# Sheet1.net
KiCad netlist of a schematic drawn in Altium Designer
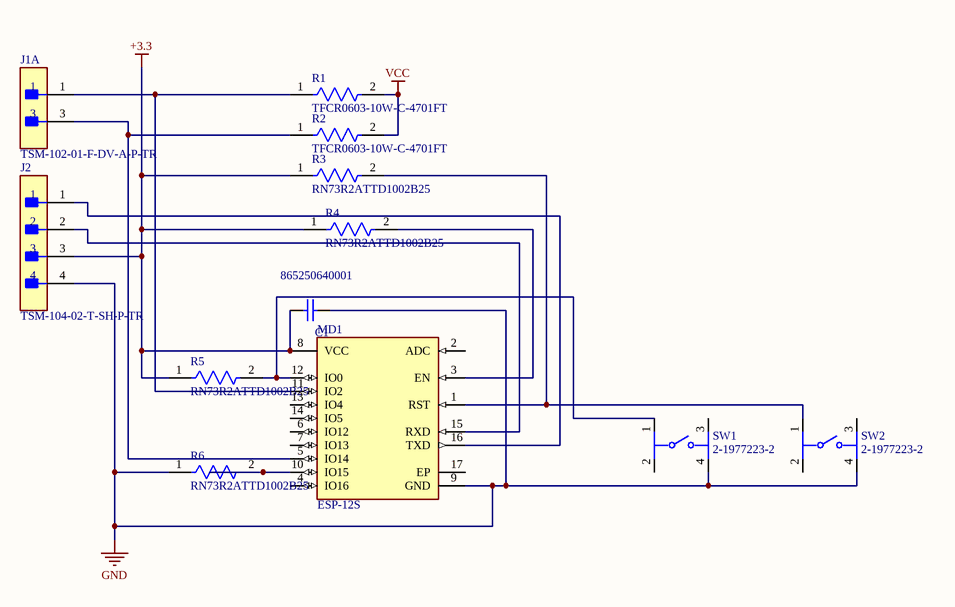
[diagram p0: Sheet1.SchDoc]

(export (version "E")
  (design (tool "Eeschema 10.0.6"))
  (components
    (comp (ref "C1")
      (value "865250640001")
      (footprint "WCAP-ASNP_D4H5.5")
      (description "WCAP-ASNP Aluminum Electrolytic Capacitors")
      (fields (field (name "TOLERANCE") "20%"))
      (libsource (lib "Altium Content Vault") (part "Capacitor_Non-Polarized"))
    )
    (comp (ref "J1")
      (value "TSM-102-01-F-DV-A-P-TR")
      (footprint "FP-TSM-102-01-F-DV-A-P-TR-MFG")
      (description "TSM-102-01-F-DV-A-P-TR .100\" Surface Mount Terminal Strip Rohs Compliant: Yes")
      (libsource (lib "Altium Content Vault") (part "1621473add15499e993d6bbd36d0f06"))
    )
    (comp (ref "J2")
      (value "TSM-104-02-T-SH-P-TR")
      (footprint "FP-TSM-104-02-T-SH-P-TR-MFG")
      (description "CONN HEADER SMD R/A 4POS 2.54MM")
      (libsource (lib "Altium Content Vault") (part "299a8cea1bdcbc3624fe62c390fa72c"))
    )
    (comp (ref "MD1")
      (value "ESP-12S")
      (footprint "FP-ESP-12S-MFG")
      (description "RX TXRX MOD WIFI PCB TRACE SMD")
      (libsource (lib "Altium Content Vault") (part "0473e498d6bc78f349d0f2898a8422c"))
    )
    (comp (ref "R1")
      (value "TFCR0603-10W-C-4701FT")
      (footprint "FP-TFCR0603-IPC_B")
      (description "RES Thin Film,  4.7kΩ, 1%, 0.1W, 50ppm/°C, 0603")
      (libsource (lib "Altium Content Vault") (part "1029c3af85768c4190bb7ad29bc67b5"))
    )
    (comp (ref "R2")
      (value "TFCR0603-10W-C-4701FT")
      (footprint "FP-TFCR0603-IPC_B")
      (description "RES Thin Film,  4.7kΩ, 1%, 0.1W, 50ppm/°C, 0603")
      (libsource (lib "Altium Content Vault") (part "1029c3af85768c4190bb7ad29bc67b5"))
    )
    (comp (ref "R3")
      (value "RN73R2ATTD1002B25")
      (footprint "FP-RN73R2A-IPC_A")
      (description "RES 10K OHM 0.1% 1/8W 0805")
      (libsource (lib "Altium Content Vault") (part "1029c3af85768c4190bb7ad29bc67b5"))
    )
    (comp (ref "R4")
      (value "RN73R2ATTD1002B25")
      (footprint "FP-RN73R2A-IPC_A")
      (description "RES 10K OHM 0.1% 1/8W 0805")
      (libsource (lib "Altium Content Vault") (part "1029c3af85768c4190bb7ad29bc67b5"))
    )
    (comp (ref "R5")
      (value "RN73R2ATTD1002B25")
      (footprint "FP-RN73R2A-IPC_A")
      (description "RES 10K OHM 0.1% 1/8W 0805")
      (libsource (lib "Altium Content Vault") (part "1029c3af85768c4190bb7ad29bc67b5"))
    )
    (comp (ref "R6")
      (value "RN73R2ATTD1002B25")
      (footprint "FP-RN73R2A-IPC_A")
      (description "RES 10K OHM 0.1% 1/8W 0805")
      (libsource (lib "Altium Content Vault") (part "1029c3af85768c4190bb7ad29bc67b5"))
    )
    (comp (ref "SW1")
      (value "2-1977223-2")
      (footprint "FP-2-1977223-2-MFG")
      (description "SWITCH TACTILE SPST-NO 0.05A 24V")
      (libsource (lib "Altium Content Vault") (part "b8895f3f4cefb76e1819d2863dba89b"))
    )
    (comp (ref "SW2")
      (value "2-1977223-2")
      (footprint "FP-2-1977223-2-MFG")
      (description "SWITCH TACTILE SPST-NO 0.05A 24V")
      (libsource (lib "Altium Content Vault") (part "b8895f3f4cefb76e1819d2863dba89b"))
    )
  )
  (nets
    (net (code "1") (name "+3.3") (class "Default")
      (node (ref "C1") (pin "2") (pinfunction "2_2") (pintype "passive"))
      (node (ref "J2") (pin "3") (pinfunction "3_3") (pintype "passive"))
      (node (ref "MD1") (pin "8") (pinfunction "VCC_8") (pintype "power_in"))
      (node (ref "R3") (pin "1") (pinfunction "1_1") (pintype "passive"))
      (node (ref "R4") (pin "1") (pinfunction "1_1") (pintype "passive"))
      (node (ref "R5") (pin "1") (pinfunction "1_1") (pintype "passive"))
    )
    (net (code "2") (name "GND") (class "Default")
      (node (ref "C1") (pin "1") (pinfunction "1_1") (pintype "passive"))
      (node (ref "J2") (pin "4") (pinfunction "4_4") (pintype "passive"))
      (node (ref "MD1") (pin "9") (pinfunction "GND_9") (pintype "power_in"))
      (node (ref "R6") (pin "1") (pinfunction "1_1") (pintype "passive"))
      (node (ref "SW1") (pin "4") (pinfunction "4_4") (pintype "passive"))
      (node (ref "SW2") (pin "4") (pinfunction "4_4") (pintype "passive"))
    )
    (net (code "3") (name "Net-(MD1-EN)") (class "Default")
      (node (ref "MD1") (pin "3") (pinfunction "EN_3") (pintype "input"))
      (node (ref "R4") (pin "2") (pinfunction "2_2") (pintype "passive"))
    )
    (net (code "4") (name "Net-(MD1-IO0)") (class "Default")
      (node (ref "MD1") (pin "12") (pinfunction "IO0_12") (pintype "bidirectional"))
      (node (ref "R5") (pin "2") (pinfunction "2_2") (pintype "passive"))
      (node (ref "SW1") (pin "1") (pinfunction "1_1") (pintype "passive"))
    )
    (net (code "5") (name "Net-(MD1-IO2)") (class "Default")
      (node (ref "J1") (pin "1") (pinfunction "1_1") (pintype "passive"))
      (node (ref "MD1") (pin "11") (pinfunction "IO2_11") (pintype "bidirectional"))
      (node (ref "R1") (pin "1") (pinfunction "1_1") (pintype "passive"))
    )
    (net (code "6") (name "Net-(MD1-IO14)") (class "Default")
      (node (ref "J1") (pin "3") (pinfunction "3_3") (pintype "passive"))
      (node (ref "MD1") (pin "5") (pinfunction "IO14_5") (pintype "bidirectional"))
      (node (ref "R2") (pin "1") (pinfunction "1_1") (pintype "passive"))
    )
    (net (code "7") (name "Net-(MD1-IO15)") (class "Default")
      (node (ref "MD1") (pin "10") (pinfunction "IO15_10") (pintype "bidirectional"))
      (node (ref "R6") (pin "2") (pinfunction "2_2") (pintype "passive"))
    )
    (net (code "8") (name "Net-(MD1-RST)") (class "Default")
      (node (ref "MD1") (pin "1") (pinfunction "RST_1") (pintype "input"))
      (node (ref "R3") (pin "2") (pinfunction "2_2") (pintype "passive"))
      (node (ref "SW2") (pin "1") (pinfunction "1_1") (pintype "passive"))
    )
    (net (code "9") (name "Net-(MD1-RXD)") (class "Default")
      (node (ref "J2") (pin "2") (pinfunction "2_2") (pintype "passive"))
      (node (ref "MD1") (pin "15") (pinfunction "RXD_15") (pintype "input"))
    )
    (net (code "10") (name "Net-(MD1-TXD)") (class "Default")
      (node (ref "J2") (pin "1") (pinfunction "1_1") (pintype "passive"))
      (node (ref "MD1") (pin "16") (pinfunction "TXD_16") (pintype "output"))
    )
    (net (code "11") (name "VCC") (class "Default")
      (node (ref "R1") (pin "2") (pinfunction "2_2") (pintype "passive"))
      (node (ref "R2") (pin "2") (pinfunction "2_2") (pintype "passive"))
    )
    (net (code "12") (name "unconnected-(MD1-ADC-Pad2)") (class "Default")
      (node (ref "MD1") (pin "2") (pinfunction "ADC_2") (pintype "input"))
    )
    (net (code "13") (name "unconnected-(MD1-EP-Pad17)") (class "Default")
      (node (ref "MD1") (pin "17") (pinfunction "EP_17") (pintype "power_in"))
    )
    (net (code "14") (name "unconnected-(MD1-IO4-Pad13)") (class "Default")
      (node (ref "MD1") (pin "13") (pinfunction "IO4_13") (pintype "bidirectional"))
    )
    (net (code "15") (name "unconnected-(MD1-IO5-Pad14)") (class "Default")
      (node (ref "MD1") (pin "14") (pinfunction "IO5_14") (pintype "bidirectional"))
    )
    (net (code "16") (name "unconnected-(MD1-IO12-Pad6)") (class "Default")
      (node (ref "MD1") (pin "6") (pinfunction "IO12_6") (pintype "bidirectional"))
    )
    (net (code "17") (name "unconnected-(MD1-IO13-Pad7)") (class "Default")
      (node (ref "MD1") (pin "7") (pinfunction "IO13_7") (pintype "bidirectional"))
    )
    (net (code "18") (name "unconnected-(MD1-IO16-Pad4)") (class "Default")
      (node (ref "MD1") (pin "4") (pinfunction "IO16_4") (pintype "bidirectional"))
    )
    (net (code "19") (name "unconnected-(SW1-Pad2)") (class "Default")
      (node (ref "SW1") (pin "2") (pinfunction "2_2") (pintype "passive"))
    )
    (net (code "20") (name "unconnected-(SW1-Pad3)") (class "Default")
      (node (ref "SW1") (pin "3") (pinfunction "3_3") (pintype "passive"))
    )
    (net (code "21") (name "unconnected-(SW2-Pad2)") (class "Default")
      (node (ref "SW2") (pin "2") (pinfunction "2_2") (pintype "passive"))
    )
    (net (code "22") (name "unconnected-(SW2-Pad3)") (class "Default")
      (node (ref "SW2") (pin "3") (pinfunction "3_3") (pintype "passive"))
    )
  )
)
